# Interface_Unit.net
KiCad netlist of a schematic drawn in Altium Designer
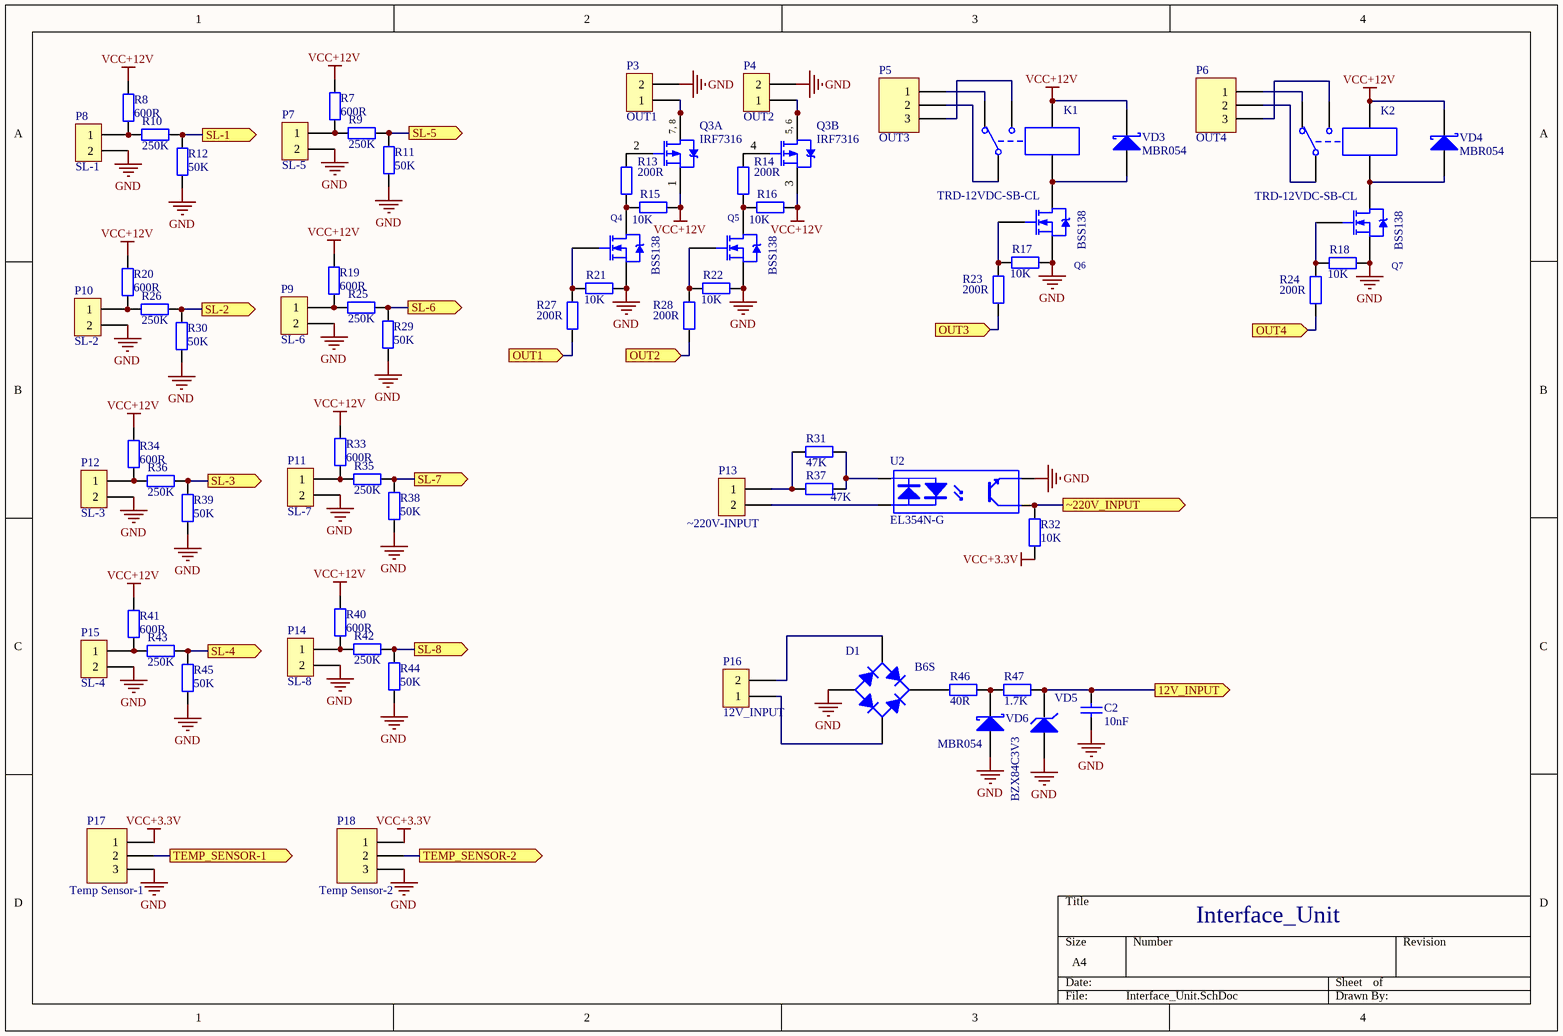
[diagram p0: Interface_Unit.SchDoc]

(export (version "E")
  (design (tool "Eeschema 10.0.6"))
  (components
    (comp (ref "C2")
      (value "10nF")
      (footprint "C0603")
      (description "Capasitor_SMD_0808/")
      (fields (field (name "Comment") "0805"))
      (libsource (lib "NEW") (part "Capasitor_SMD_0805"))
    )
    (comp (ref "D1")
      (value "B6S")
      (footprint "B6S")
      (description "Diode Bridge")
      (libsource (lib "NEW") (part "B6S"))
    )
    (comp (ref "K1")
      (value "TRD-12VDC-SB-CL")
      (footprint "TRD-C Type")
      (libsource (lib "NEW") (part "TRD-12VDC-SB-CL"))
    )
    (comp (ref "K2")
      (value "TRD-12VDC-SB-CL")
      (footprint "TRD-C Type")
      (libsource (lib "NEW") (part "TRD-12VDC-SB-CL"))
    )
    (comp (ref "P3")
      (value "15EDGRC-3.5-02P")
      (footprint "15EDGRC-3.5-02P")
      (fields (field (name "ALTIUM_UNNAMED_1") "OUT1"))
      (libsource (lib "") (part "15EDGRC-3.5-02P_1"))
    )
    (comp (ref "P4")
      (value "15EDGRC-3.5-02P")
      (footprint "15EDGRC-3.5-02P")
      (fields (field (name "ALTIUM_UNNAMED_1") "OUT2"))
      (libsource (lib "") (part "15EDGRC-3.5-02P_1"))
    )
    (comp (ref "P5")
      (value "OUT3")
      (footprint "15EDGRC-3.5-03P")
      (libsource (lib "NEW") (part "15EDGRC-3.5-03P"))
    )
    (comp (ref "P6")
      (value "OUT4")
      (footprint "15EDGRC-3.5-03P")
      (libsource (lib "NEW") (part "15EDGRC-3.5-03P"))
    )
    (comp (ref "P7")
      (value "15EDGRC-3.5-02P")
      (footprint "15EDGRC-3.5-02P")
      (fields (field (name "ALTIUM_UNNAMED_1") "SL-5"))
      (libsource (lib "NEW") (part "15EDGRC-3.5-02P"))
    )
    (comp (ref "P8")
      (value "15EDGRC-3.5-02P")
      (footprint "15EDGRC-3.5-02P")
      (fields (field (name "ALTIUM_UNNAMED_1") "SL-1"))
      (libsource (lib "NEW") (part "15EDGRC-3.5-02P"))
    )
    (comp (ref "P9")
      (value "15EDGRC-3.5-02P")
      (footprint "15EDGRC-3.5-02P")
      (fields (field (name "ALTIUM_UNNAMED_1") "SL-6"))
      (libsource (lib "NEW") (part "15EDGRC-3.5-02P"))
    )
    (comp (ref "P10")
      (value "15EDGRC-3.5-02P")
      (footprint "15EDGRC-3.5-02P")
      (fields (field (name "ALTIUM_UNNAMED_1") "SL-2"))
      (libsource (lib "NEW") (part "15EDGRC-3.5-02P"))
    )
    (comp (ref "P11")
      (value "15EDGRC-3.5-02P")
      (footprint "15EDGRC-3.5-02P")
      (fields (field (name "ALTIUM_UNNAMED_1") "SL-7"))
      (libsource (lib "NEW") (part "15EDGRC-3.5-02P"))
    )
    (comp (ref "P12")
      (value "15EDGRC-3.5-02P")
      (footprint "15EDGRC-3.5-02P")
      (fields (field (name "ALTIUM_UNNAMED_1") "SL-3"))
      (libsource (lib "NEW") (part "15EDGRC-3.5-02P"))
    )
    (comp (ref "P13")
      (value "15EDGRC-3.5-02P")
      (footprint "15EDGRC-3.5-02P")
      (fields (field (name "ALTIUM_UNNAMED_1") "~220V-INPUT"))
      (libsource (lib "NEW") (part "15EDGRC-3.5-02P"))
    )
    (comp (ref "P14")
      (value "15EDGRC-3.5-02P")
      (footprint "15EDGRC-3.5-02P")
      (fields (field (name "ALTIUM_UNNAMED_1") "SL-8"))
      (libsource (lib "NEW") (part "15EDGRC-3.5-02P"))
    )
    (comp (ref "P15")
      (value "15EDGRC-3.5-02P")
      (footprint "15EDGRC-3.5-02P")
      (fields (field (name "ALTIUM_UNNAMED_1") "SL-4"))
      (libsource (lib "NEW") (part "15EDGRC-3.5-02P"))
    )
    (comp (ref "P16")
      (value "15EDGRC-3.5-02P")
      (footprint "15EDGRC-3.5-02P")
      (fields (field (name "ALTIUM_UNNAMED_1") "12V_INPUT"))
      (libsource (lib "") (part "15EDGRC-3.5-02P_1"))
    )
    (comp (ref "P17")
      (value "Temp Sensor-1")
      (footprint "15EDGRC-3.5-03P")
      (libsource (lib "NEW") (part "15EDGRC-3.5-03P"))
    )
    (comp (ref "P18")
      (value "Temp Sensor-2")
      (footprint "15EDGRC-3.5-03P")
      (libsource (lib "NEW") (part "15EDGRC-3.5-03P"))
    )
    (comp (ref "Q3")
      (value "IRF7316")
      (footprint "SO-8_N")
      (description "HEXFET Power MOSFET")
      (fields (field (name "PUBLISHER") "Altium Limited"))
      (libsource (lib "IR Discrete MOSFET - Power") (part "IRF7316"))
    )
    (comp (ref "Q4")
      (value "BSS138")
      (footprint "SOT23")
      (description "BSS138-SOT23")
      (libsource (lib "NEW") (part "BSS138-SOT23"))
    )
    (comp (ref "Q5")
      (value "BSS138")
      (footprint "SOT23")
      (description "BSS138-SOT23")
      (libsource (lib "NEW") (part "BSS138-SOT23"))
    )
    (comp (ref "Q6")
      (value "BSS138")
      (footprint "SOT23")
      (description "BSS138-SOT23")
      (libsource (lib "NEW") (part "BSS138-SOT23"))
    )
    (comp (ref "Q7")
      (value "BSS138")
      (footprint "SOT23")
      (description "BSS138-SOT23")
      (libsource (lib "NEW") (part "BSS138-SOT23"))
    )
    (comp (ref "R7")
      (value "600R")
      (footprint "SMD-1206")
      (description "Resistor")
      (fields (field (name "Comment") "RES_SMD"))
      (libsource (lib "") (part "RES_1"))
    )
    (comp (ref "R8")
      (value "600R")
      (footprint "SMD-1206")
      (description "Resistor")
      (fields (field (name "Comment") "RES_SMD"))
      (libsource (lib "") (part "RES_1"))
    )
    (comp (ref "R9")
      (value "250K")
      (footprint "C0603")
      (description "Resistor")
      (fields (field (name "Comment") "RES_SMD"))
      (libsource (lib "NEW") (part "RES"))
    )
    (comp (ref "R10")
      (value "250K")
      (footprint "C0603")
      (description "Resistor")
      (fields (field (name "Comment") "RES_SMD"))
      (libsource (lib "NEW") (part "RES"))
    )
    (comp (ref "R11")
      (value "50K")
      (footprint "C0603")
      (description "Resistor")
      (fields (field (name "Comment") "RES_SMD"))
      (libsource (lib "") (part "RES_1"))
    )
    (comp (ref "R12")
      (value "50K")
      (footprint "C0603")
      (description "Resistor")
      (fields (field (name "Comment") "RES_SMD"))
      (libsource (lib "") (part "RES_1"))
    )
    (comp (ref "R13")
      (value "200R")
      (footprint "C0603")
      (description "Resistor")
      (fields (field (name "Comment") "RES_SMD"))
      (libsource (lib "") (part "RES_1"))
    )
    (comp (ref "R14")
      (value "200R")
      (footprint "C0603")
      (description "Resistor")
      (fields (field (name "Comment") "RES_SMD"))
      (libsource (lib "") (part "RES_1"))
    )
    (comp (ref "R15")
      (value "10K")
      (footprint "C0603")
      (description "Resistor")
      (fields (field (name "Comment") "RES_SMD"))
      (libsource (lib "NEW") (part "RES"))
    )
    (comp (ref "R16")
      (value "10K")
      (footprint "C0603")
      (description "Resistor")
      (fields (field (name "Comment") "RES_SMD"))
      (libsource (lib "NEW") (part "RES"))
    )
    (comp (ref "R17")
      (value "10K")
      (footprint "C0603")
      (description "Resistor")
      (fields (field (name "Comment") "RES_SMD"))
      (libsource (lib "NEW") (part "RES"))
    )
    (comp (ref "R18")
      (value "10K")
      (footprint "C0603")
      (description "Resistor")
      (fields (field (name "Comment") "RES_SMD"))
      (libsource (lib "NEW") (part "RES"))
    )
    (comp (ref "R19")
      (value "600R")
      (footprint "SMD-1206")
      (description "Resistor")
      (fields (field (name "Comment") "RES_SMD"))
      (libsource (lib "") (part "RES_1"))
    )
    (comp (ref "R20")
      (value "600R")
      (footprint "SMD-1206")
      (description "Resistor")
      (fields (field (name "Comment") "RES_SMD"))
      (libsource (lib "") (part "RES_1"))
    )
    (comp (ref "R21")
      (value "10K")
      (footprint "C0603")
      (description "Resistor")
      (fields (field (name "Comment") "RES_SMD"))
      (libsource (lib "NEW") (part "RES"))
    )
    (comp (ref "R22")
      (value "10K")
      (footprint "C0603")
      (description "Resistor")
      (fields (field (name "Comment") "RES_SMD"))
      (libsource (lib "NEW") (part "RES"))
    )
    (comp (ref "R23")
      (value "200R")
      (footprint "C0603")
      (description "Resistor")
      (fields (field (name "Comment") "RES_SMD"))
      (libsource (lib "") (part "RES_1"))
    )
    (comp (ref "R24")
      (value "200R")
      (footprint "C0603")
      (description "Resistor")
      (fields (field (name "Comment") "RES_SMD"))
      (libsource (lib "") (part "RES_1"))
    )
    (comp (ref "R25")
      (value "250K")
      (footprint "C0603")
      (description "Resistor")
      (fields (field (name "Comment") "RES_SMD"))
      (libsource (lib "NEW") (part "RES"))
    )
    (comp (ref "R26")
      (value "250K")
      (footprint "C0603")
      (description "Resistor")
      (fields (field (name "Comment") "RES_SMD"))
      (libsource (lib "NEW") (part "RES"))
    )
    (comp (ref "R27")
      (value "200R")
      (footprint "C0603")
      (description "Resistor")
      (fields (field (name "Comment") "RES_SMD"))
      (libsource (lib "") (part "RES_1"))
    )
    (comp (ref "R28")
      (value "200R")
      (footprint "C0603")
      (description "Resistor")
      (fields (field (name "Comment") "RES_SMD"))
      (libsource (lib "") (part "RES_1"))
    )
    (comp (ref "R29")
      (value "50K")
      (footprint "C0603")
      (description "Resistor")
      (fields (field (name "Comment") "RES_SMD"))
      (libsource (lib "") (part "RES_1"))
    )
    (comp (ref "R30")
      (value "50K")
      (footprint "C0603")
      (description "Resistor")
      (fields (field (name "Comment") "RES_SMD"))
      (libsource (lib "") (part "RES_1"))
    )
    (comp (ref "R31")
      (value "47K")
      (footprint "SMD-2512")
      (description "Resistor")
      (fields (field (name "Comment") "RES_SMD"))
      (libsource (lib "NEW") (part "RES"))
    )
    (comp (ref "R32")
      (value "10K")
      (footprint "C0603")
      (description "Resistor")
      (fields (field (name "Comment") "RES_SMD"))
      (libsource (lib "") (part "RES_1"))
    )
    (comp (ref "R33")
      (value "600R")
      (footprint "SMD-1206")
      (description "Resistor")
      (fields (field (name "Comment") "RES_SMD"))
      (libsource (lib "") (part "RES_1"))
    )
    (comp (ref "R34")
      (value "600R")
      (footprint "SMD-1206")
      (description "Resistor")
      (fields (field (name "Comment") "RES_SMD"))
      (libsource (lib "") (part "RES_1"))
    )
    (comp (ref "R35")
      (value "250K")
      (footprint "C0603")
      (description "Resistor")
      (fields (field (name "Comment") "RES_SMD"))
      (libsource (lib "NEW") (part "RES"))
    )
    (comp (ref "R36")
      (value "250K")
      (footprint "C0603")
      (description "Resistor")
      (fields (field (name "Comment") "RES_SMD"))
      (libsource (lib "NEW") (part "RES"))
    )
    (comp (ref "R37")
      (value "47K")
      (footprint "SMD-2512")
      (description "Resistor")
      (fields (field (name "Comment") "RES_SMD"))
      (libsource (lib "NEW") (part "RES"))
    )
    (comp (ref "R38")
      (value "50K")
      (footprint "C0603")
      (description "Resistor")
      (fields (field (name "Comment") "RES_SMD"))
      (libsource (lib "") (part "RES_1"))
    )
    (comp (ref "R39")
      (value "50K")
      (footprint "C0603")
      (description "Resistor")
      (fields (field (name "Comment") "RES_SMD"))
      (libsource (lib "") (part "RES_1"))
    )
    (comp (ref "R40")
      (value "600R")
      (footprint "SMD-1206")
      (description "Resistor")
      (fields (field (name "Comment") "RES_SMD"))
      (libsource (lib "") (part "RES_1"))
    )
    (comp (ref "R41")
      (value "600R")
      (footprint "SMD-1206")
      (description "Resistor")
      (fields (field (name "Comment") "RES_SMD"))
      (libsource (lib "") (part "RES_1"))
    )
    (comp (ref "R42")
      (value "250K")
      (footprint "C0603")
      (description "Resistor")
      (fields (field (name "Comment") "RES_SMD"))
      (libsource (lib "NEW") (part "RES"))
    )
    (comp (ref "R43")
      (value "250K")
      (footprint "C0603")
      (description "Resistor")
      (fields (field (name "Comment") "RES_SMD"))
      (libsource (lib "NEW") (part "RES"))
    )
    (comp (ref "R44")
      (value "50K")
      (footprint "C0603")
      (description "Resistor")
      (fields (field (name "Comment") "RES_SMD"))
      (libsource (lib "") (part "RES_1"))
    )
    (comp (ref "R45")
      (value "50K")
      (footprint "C0603")
      (description "Resistor")
      (fields (field (name "Comment") "RES_SMD"))
      (libsource (lib "") (part "RES_1"))
    )
    (comp (ref "R46")
      (value "40R")
      (footprint "C0805")
      (description "Resistor")
      (fields (field (name "Comment") "RES"))
      (libsource (lib "NEW") (part "RES"))
    )
    (comp (ref "R47")
      (value "1.7K")
      (footprint "C0805")
      (description "Resistor")
      (fields (field (name "Comment") "RES"))
      (libsource (lib "NEW") (part "RES"))
    )
    (comp (ref "U2") (value "EL354N-G") (footprint "EL354N-G") (libsource (lib "NEW") (part "EL354N")))
    (comp (ref "VD3") (value "MBR054") (footprint "SOD-123") (libsource (lib "NEW") (part "MBR054")))
    (comp (ref "VD4") (value "MBR054") (footprint "SOD-123") (libsource (lib "NEW") (part "MBR054")))
    (comp (ref "VD5")
      (value "BZX84C3V3")
      (footprint "SOT23")
      (description "BZX84C")
      (libsource (lib "NEW") (part "BZX84C"))
    )
    (comp (ref "VD6") (value "MBR054") (footprint "SOD-123") (libsource (lib "NEW") (part "MBR054")))
  )
  (nets
    (net (code "1") (name "/12V_INPUT") (class "Default")
      (node (ref "C2") (pin "1") (pinfunction "1_1") (pintype "passive"))
      (node (ref "R47") (pin "2") (pinfunction "2_2") (pintype "passive"))
      (node (ref "VD5") (pin "3") (pinfunction "K_3") (pintype "passive"))
    )
    (net (code "2") (name "/OUT1") (class "Default")
      (node (ref "R27") (pin "1") (pinfunction "1_1") (pintype "passive"))
    )
    (net (code "3") (name "/OUT2") (class "Default")
      (node (ref "R28") (pin "1") (pinfunction "1_1") (pintype "passive"))
    )
    (net (code "4") (name "/OUT3") (class "Default")
      (node (ref "R23") (pin "1") (pinfunction "1_1") (pintype "passive"))
    )
    (net (code "5") (name "/OUT4") (class "Default")
      (node (ref "R24") (pin "1") (pinfunction "1_1") (pintype "passive"))
    )
    (net (code "6") (name "/SL-1") (class "Default")
      (node (ref "R10") (pin "2") (pinfunction "2_2") (pintype "passive"))
      (node (ref "R12") (pin "2") (pinfunction "2_2") (pintype "passive"))
    )
    (net (code "7") (name "/SL-2") (class "Default")
      (node (ref "R26") (pin "2") (pinfunction "2_2") (pintype "passive"))
      (node (ref "R30") (pin "2") (pinfunction "2_2") (pintype "passive"))
    )
    (net (code "8") (name "/SL-3") (class "Default")
      (node (ref "R36") (pin "2") (pinfunction "2_2") (pintype "passive"))
      (node (ref "R39") (pin "2") (pinfunction "2_2") (pintype "passive"))
    )
    (net (code "9") (name "/SL-4") (class "Default")
      (node (ref "R43") (pin "2") (pinfunction "2_2") (pintype "passive"))
      (node (ref "R45") (pin "2") (pinfunction "2_2") (pintype "passive"))
    )
    (net (code "10") (name "/SL-5") (class "Default")
      (node (ref "R11") (pin "2") (pinfunction "2_2") (pintype "passive"))
      (node (ref "R9") (pin "2") (pinfunction "2_2") (pintype "passive"))
    )
    (net (code "11") (name "/SL-6") (class "Default")
      (node (ref "R25") (pin "2") (pinfunction "2_2") (pintype "passive"))
      (node (ref "R29") (pin "2") (pinfunction "2_2") (pintype "passive"))
    )
    (net (code "12") (name "/SL-7") (class "Default")
      (node (ref "R35") (pin "2") (pinfunction "2_2") (pintype "passive"))
      (node (ref "R38") (pin "2") (pinfunction "2_2") (pintype "passive"))
    )
    (net (code "13") (name "/SL-8") (class "Default")
      (node (ref "R42") (pin "2") (pinfunction "2_2") (pintype "passive"))
      (node (ref "R44") (pin "2") (pinfunction "2_2") (pintype "passive"))
    )
    (net (code "14") (name "/TEMP_SENSOR-1") (class "Default")
      (node (ref "P17") (pin "2") (pinfunction "2_2") (pintype "passive"))
    )
    (net (code "15") (name "/TEMP_SENSOR-2") (class "Default")
      (node (ref "P18") (pin "2") (pinfunction "2_2") (pintype "passive"))
    )
    (net (code "16") (name "/~220V_INPUT") (class "Default")
      (node (ref "R32") (pin "2") (pinfunction "2_2") (pintype "passive"))
      (node (ref "U2") (pin "4") (pinfunction "4_4") (pintype "passive"))
    )
    (net (code "17") (name "GND") (class "Default")
      (node (ref "C2") (pin "2") (pinfunction "2_2") (pintype "passive"))
      (node (ref "D1") (pin "3") (pinfunction "A_3") (pintype "passive"))
      (node (ref "P10") (pin "2") (pinfunction "2_2") (pintype "passive"))
      (node (ref "P11") (pin "2") (pinfunction "2_2") (pintype "passive"))
      (node (ref "P12") (pin "2") (pinfunction "2_2") (pintype "passive"))
      (node (ref "P14") (pin "2") (pinfunction "2_2") (pintype "passive"))
      (node (ref "P15") (pin "2") (pinfunction "2_2") (pintype "passive"))
      (node (ref "P17") (pin "3") (pinfunction "3_3") (pintype "passive"))
      (node (ref "P18") (pin "3") (pinfunction "3_3") (pintype "passive"))
      (node (ref "P3") (pin "2") (pinfunction "2_2") (pintype "passive"))
      (node (ref "P4") (pin "2") (pinfunction "2_2") (pintype "passive"))
      (node (ref "P7") (pin "2") (pinfunction "2_2") (pintype "passive"))
      (node (ref "P8") (pin "2") (pinfunction "2_2") (pintype "passive"))
      (node (ref "P9") (pin "2") (pinfunction "2_2") (pintype "passive"))
      (node (ref "Q4") (pin "2") (pinfunction "S_2") (pintype "passive"))
      (node (ref "Q5") (pin "2") (pinfunction "S_2") (pintype "passive"))
      (node (ref "Q6") (pin "2") (pinfunction "S_2") (pintype "passive"))
      (node (ref "Q7") (pin "2") (pinfunction "S_2") (pintype "passive"))
      (node (ref "R11") (pin "1") (pinfunction "1_1") (pintype "passive"))
      (node (ref "R12") (pin "1") (pinfunction "1_1") (pintype "passive"))
      (node (ref "R17") (pin "2") (pinfunction "2_2") (pintype "passive"))
      (node (ref "R18") (pin "2") (pinfunction "2_2") (pintype "passive"))
      (node (ref "R21") (pin "2") (pinfunction "2_2") (pintype "passive"))
      (node (ref "R22") (pin "2") (pinfunction "2_2") (pintype "passive"))
      (node (ref "R29") (pin "1") (pinfunction "1_1") (pintype "passive"))
      (node (ref "R30") (pin "1") (pinfunction "1_1") (pintype "passive"))
      (node (ref "R38") (pin "1") (pinfunction "1_1") (pintype "passive"))
      (node (ref "R39") (pin "1") (pinfunction "1_1") (pintype "passive"))
      (node (ref "R44") (pin "1") (pinfunction "1_1") (pintype "passive"))
      (node (ref "R45") (pin "1") (pinfunction "1_1") (pintype "passive"))
      (node (ref "U2") (pin "3") (pinfunction "3_3") (pintype "passive"))
      (node (ref "VD5") (pin "1") (pinfunction "A_1") (pintype "passive"))
      (node (ref "VD6") (pin "2") (pinfunction "A_2") (pintype "passive"))
    )
    (net (code "18") (name "Net-(D1-C-Pad2)") (class "Default")
      (node (ref "D1") (pin "2") (pinfunction "C_2") (pintype "passive"))
      (node (ref "P16") (pin "1") (pinfunction "1_1") (pintype "passive"))
    )
    (net (code "19") (name "Net-(D1-C-Pad4)") (class "Default")
      (node (ref "D1") (pin "4") (pinfunction "C_4") (pintype "passive"))
      (node (ref "P16") (pin "2") (pinfunction "2_2") (pintype "passive"))
    )
    (net (code "20") (name "Net-(D1-K)") (class "Default")
      (node (ref "D1") (pin "1") (pinfunction "K_1") (pintype "passive"))
      (node (ref "R46") (pin "1") (pinfunction "1_1") (pintype "passive"))
    )
    (net (code "21") (name "Net-(K1-Pad3)") (class "Default")
      (node (ref "K1") (pin "3") (pinfunction "3_3") (pintype "passive"))
      (node (ref "P5") (pin "2") (pinfunction "2_2") (pintype "passive"))
    )
    (net (code "22") (name "Net-(K1-Pad4)") (class "Default")
      (node (ref "K1") (pin "4") (pinfunction "4_4") (pintype "passive"))
      (node (ref "P5") (pin "1") (pinfunction "1_1") (pintype "passive"))
    )
    (net (code "23") (name "Net-(K1-Pad5)") (class "Default")
      (node (ref "K1") (pin "5") (pinfunction "5_5") (pintype "passive"))
      (node (ref "P5") (pin "3") (pinfunction "3_3") (pintype "passive"))
    )
    (net (code "24") (name "Net-(K2-Pad3)") (class "Default")
      (node (ref "K2") (pin "3") (pinfunction "3_3") (pintype "passive"))
      (node (ref "P6") (pin "2") (pinfunction "2_2") (pintype "passive"))
    )
    (net (code "25") (name "Net-(K2-Pad4)") (class "Default")
      (node (ref "K2") (pin "4") (pinfunction "4_4") (pintype "passive"))
      (node (ref "P6") (pin "1") (pinfunction "1_1") (pintype "passive"))
    )
    (net (code "26") (name "Net-(K2-Pad5)") (class "Default")
      (node (ref "K2") (pin "5") (pinfunction "5_5") (pintype "passive"))
      (node (ref "P6") (pin "3") (pinfunction "3_3") (pintype "passive"))
    )
    (net (code "27") (name "Net-(P3-Pad1)") (class "Default")
      (node (ref "P3") (pin "1") (pinfunction "1_1") (pintype "passive"))
      (node (ref "Q3") (pin "7") (pinfunction "D_7") (pintype "passive"))
      (node (ref "Q3") (pin "8") (pinfunction "D_8") (pintype "passive"))
    )
    (net (code "28") (name "Net-(P4-Pad1)") (class "Default")
      (node (ref "P4") (pin "1") (pinfunction "1_1") (pintype "passive"))
      (node (ref "Q3") (pin "5") (pinfunction "D_5") (pintype "passive"))
      (node (ref "Q3") (pin "6") (pinfunction "D_6") (pintype "passive"))
    )
    (net (code "29") (name "Net-(P7-Pad1)") (class "Default")
      (node (ref "P7") (pin "1") (pinfunction "1_1") (pintype "passive"))
      (node (ref "R7") (pin "1") (pinfunction "1_1") (pintype "passive"))
      (node (ref "R9") (pin "1") (pinfunction "1_1") (pintype "passive"))
    )
    (net (code "30") (name "Net-(P8-Pad1)") (class "Default")
      (node (ref "P8") (pin "1") (pinfunction "1_1") (pintype "passive"))
      (node (ref "R10") (pin "1") (pinfunction "1_1") (pintype "passive"))
      (node (ref "R8") (pin "1") (pinfunction "1_1") (pintype "passive"))
    )
    (net (code "31") (name "Net-(P9-Pad1)") (class "Default")
      (node (ref "P9") (pin "1") (pinfunction "1_1") (pintype "passive"))
      (node (ref "R19") (pin "1") (pinfunction "1_1") (pintype "passive"))
      (node (ref "R25") (pin "1") (pinfunction "1_1") (pintype "passive"))
    )
    (net (code "32") (name "Net-(P10-Pad1)") (class "Default")
      (node (ref "P10") (pin "1") (pinfunction "1_1") (pintype "passive"))
      (node (ref "R20") (pin "1") (pinfunction "1_1") (pintype "passive"))
      (node (ref "R26") (pin "1") (pinfunction "1_1") (pintype "passive"))
    )
    (net (code "33") (name "Net-(P11-Pad1)") (class "Default")
      (node (ref "P11") (pin "1") (pinfunction "1_1") (pintype "passive"))
      (node (ref "R33") (pin "1") (pinfunction "1_1") (pintype "passive"))
      (node (ref "R35") (pin "1") (pinfunction "1_1") (pintype "passive"))
    )
    (net (code "34") (name "Net-(P12-Pad1)") (class "Default")
      (node (ref "P12") (pin "1") (pinfunction "1_1") (pintype "passive"))
      (node (ref "R34") (pin "1") (pinfunction "1_1") (pintype "passive"))
      (node (ref "R36") (pin "1") (pinfunction "1_1") (pintype "passive"))
    )
    (net (code "35") (name "Net-(P13-Pad1)") (class "Default")
      (node (ref "P13") (pin "1") (pinfunction "1_1") (pintype "passive"))
      (node (ref "R31") (pin "1") (pinfunction "1_1") (pintype "passive"))
      (node (ref "R37") (pin "1") (pinfunction "1_1") (pintype "passive"))
    )
    (net (code "36") (name "Net-(P13-Pad2)") (class "Default")
      (node (ref "P13") (pin "2") (pinfunction "2_2") (pintype "passive"))
      (node (ref "U2") (pin "1") (pinfunction "1_1") (pintype "passive"))
    )
    (net (code "37") (name "Net-(P14-Pad1)") (class "Default")
      (node (ref "P14") (pin "1") (pinfunction "1_1") (pintype "passive"))
      (node (ref "R40") (pin "1") (pinfunction "1_1") (pintype "passive"))
      (node (ref "R42") (pin "1") (pinfunction "1_1") (pintype "passive"))
    )
    (net (code "38") (name "Net-(P15-Pad1)") (class "Default")
      (node (ref "P15") (pin "1") (pinfunction "1_1") (pintype "passive"))
      (node (ref "R41") (pin "1") (pinfunction "1_1") (pintype "passive"))
      (node (ref "R43") (pin "1") (pinfunction "1_1") (pintype "passive"))
    )
    (net (code "39") (name "Net-(Q3A-G)") (class "Default")
      (node (ref "Q3") (pin "2") (pinfunction "G_2") (pintype "passive"))
      (node (ref "R13") (pin "2") (pinfunction "2_2") (pintype "passive"))
    )
    (net (code "40") (name "Net-(Q3B-G)") (class "Default")
      (node (ref "Q3") (pin "4") (pinfunction "G_4") (pintype "passive"))
      (node (ref "R14") (pin "2") (pinfunction "2_2") (pintype "passive"))
    )
    (net (code "41") (name "Net-(Q4-D)") (class "Default")
      (node (ref "Q4") (pin "3") (pinfunction "D_3") (pintype "passive"))
      (node (ref "R13") (pin "1") (pinfunction "1_1") (pintype "passive"))
      (node (ref "R15") (pin "1") (pinfunction "1_1") (pintype "passive"))
    )
    (net (code "42") (name "Net-(Q4-G)") (class "Default")
      (node (ref "Q4") (pin "1") (pinfunction "G_1") (pintype "passive"))
      (node (ref "R21") (pin "1") (pinfunction "1_1") (pintype "passive"))
      (node (ref "R27") (pin "2") (pinfunction "2_2") (pintype "passive"))
    )
    (net (code "43") (name "Net-(Q5-D)") (class "Default")
      (node (ref "Q5") (pin "3") (pinfunction "D_3") (pintype "passive"))
      (node (ref "R14") (pin "1") (pinfunction "1_1") (pintype "passive"))
      (node (ref "R16") (pin "1") (pinfunction "1_1") (pintype "passive"))
    )
    (net (code "44") (name "Net-(Q5-G)") (class "Default")
      (node (ref "Q5") (pin "1") (pinfunction "G_1") (pintype "passive"))
      (node (ref "R22") (pin "1") (pinfunction "1_1") (pintype "passive"))
      (node (ref "R28") (pin "2") (pinfunction "2_2") (pintype "passive"))
    )
    (net (code "45") (name "Net-(Q6-D)") (class "Default")
      (node (ref "K1") (pin "1") (pinfunction "1_1") (pintype "passive"))
      (node (ref "Q6") (pin "3") (pinfunction "D_3") (pintype "passive"))
      (node (ref "VD3") (pin "2") (pinfunction "A_2") (pintype "passive"))
    )
    (net (code "46") (name "Net-(Q6-G)") (class "Default")
      (node (ref "Q6") (pin "1") (pinfunction "G_1") (pintype "passive"))
      (node (ref "R17") (pin "1") (pinfunction "1_1") (pintype "passive"))
      (node (ref "R23") (pin "2") (pinfunction "2_2") (pintype "passive"))
    )
    (net (code "47") (name "Net-(Q7-D)") (class "Default")
      (node (ref "K2") (pin "1") (pinfunction "1_1") (pintype "passive"))
      (node (ref "Q7") (pin "3") (pinfunction "D_3") (pintype "passive"))
      (node (ref "VD4") (pin "2") (pinfunction "A_2") (pintype "passive"))
    )
    (net (code "48") (name "Net-(Q7-G)") (class "Default")
      (node (ref "Q7") (pin "1") (pinfunction "G_1") (pintype "passive"))
      (node (ref "R18") (pin "1") (pinfunction "1_1") (pintype "passive"))
      (node (ref "R24") (pin "2") (pinfunction "2_2") (pintype "passive"))
    )
    (net (code "49") (name "Net-(R31-Pad2)") (class "Default")
      (node (ref "R31") (pin "2") (pinfunction "2_2") (pintype "passive"))
      (node (ref "R37") (pin "2") (pinfunction "2_2") (pintype "passive"))
      (node (ref "U2") (pin "2") (pinfunction "2_2") (pintype "passive"))
    )
    (net (code "50") (name "Net-(VD6-K)") (class "Default")
      (node (ref "R46") (pin "2") (pinfunction "2_2") (pintype "passive"))
      (node (ref "R47") (pin "1") (pinfunction "1_1") (pintype "passive"))
      (node (ref "VD6") (pin "1") (pinfunction "K_1") (pintype "passive"))
    )
    (net (code "51") (name "VCC+3.3V") (class "Default")
      (node (ref "P17") (pin "1") (pinfunction "1_1") (pintype "passive"))
      (node (ref "P18") (pin "1") (pinfunction "1_1") (pintype "passive"))
      (node (ref "R32") (pin "1") (pinfunction "1_1") (pintype "passive"))
    )
    (net (code "52") (name "VCC+12V") (class "Default")
      (node (ref "K1") (pin "2") (pinfunction "2_2") (pintype "passive"))
      (node (ref "K2") (pin "2") (pinfunction "2_2") (pintype "passive"))
      (node (ref "Q3") (pin "1") (pinfunction "S_1") (pintype "passive"))
      (node (ref "Q3") (pin "3") (pinfunction "S_3") (pintype "passive"))
      (node (ref "R15") (pin "2") (pinfunction "2_2") (pintype "passive"))
      (node (ref "R16") (pin "2") (pinfunction "2_2") (pintype "passive"))
      (node (ref "R19") (pin "2") (pinfunction "2_2") (pintype "passive"))
      (node (ref "R20") (pin "2") (pinfunction "2_2") (pintype "passive"))
      (node (ref "R33") (pin "2") (pinfunction "2_2") (pintype "passive"))
      (node (ref "R34") (pin "2") (pinfunction "2_2") (pintype "passive"))
      (node (ref "R40") (pin "2") (pinfunction "2_2") (pintype "passive"))
      (node (ref "R41") (pin "2") (pinfunction "2_2") (pintype "passive"))
      (node (ref "R7") (pin "2") (pinfunction "2_2") (pintype "passive"))
      (node (ref "R8") (pin "2") (pinfunction "2_2") (pintype "passive"))
      (node (ref "VD3") (pin "1") (pinfunction "K_1") (pintype "passive"))
      (node (ref "VD4") (pin "1") (pinfunction "K_1") (pintype "passive"))
    )
    (net (code "53") (name "unconnected-(VD5-Pad2)") (class "Default")
      (node (ref "VD5") (pin "2") (pintype "passive"))
    )
  )
)
